# SCH_Hub-UDB_2025-02-06.net
KiCad netlist of a schematic drawn in EasyEDA
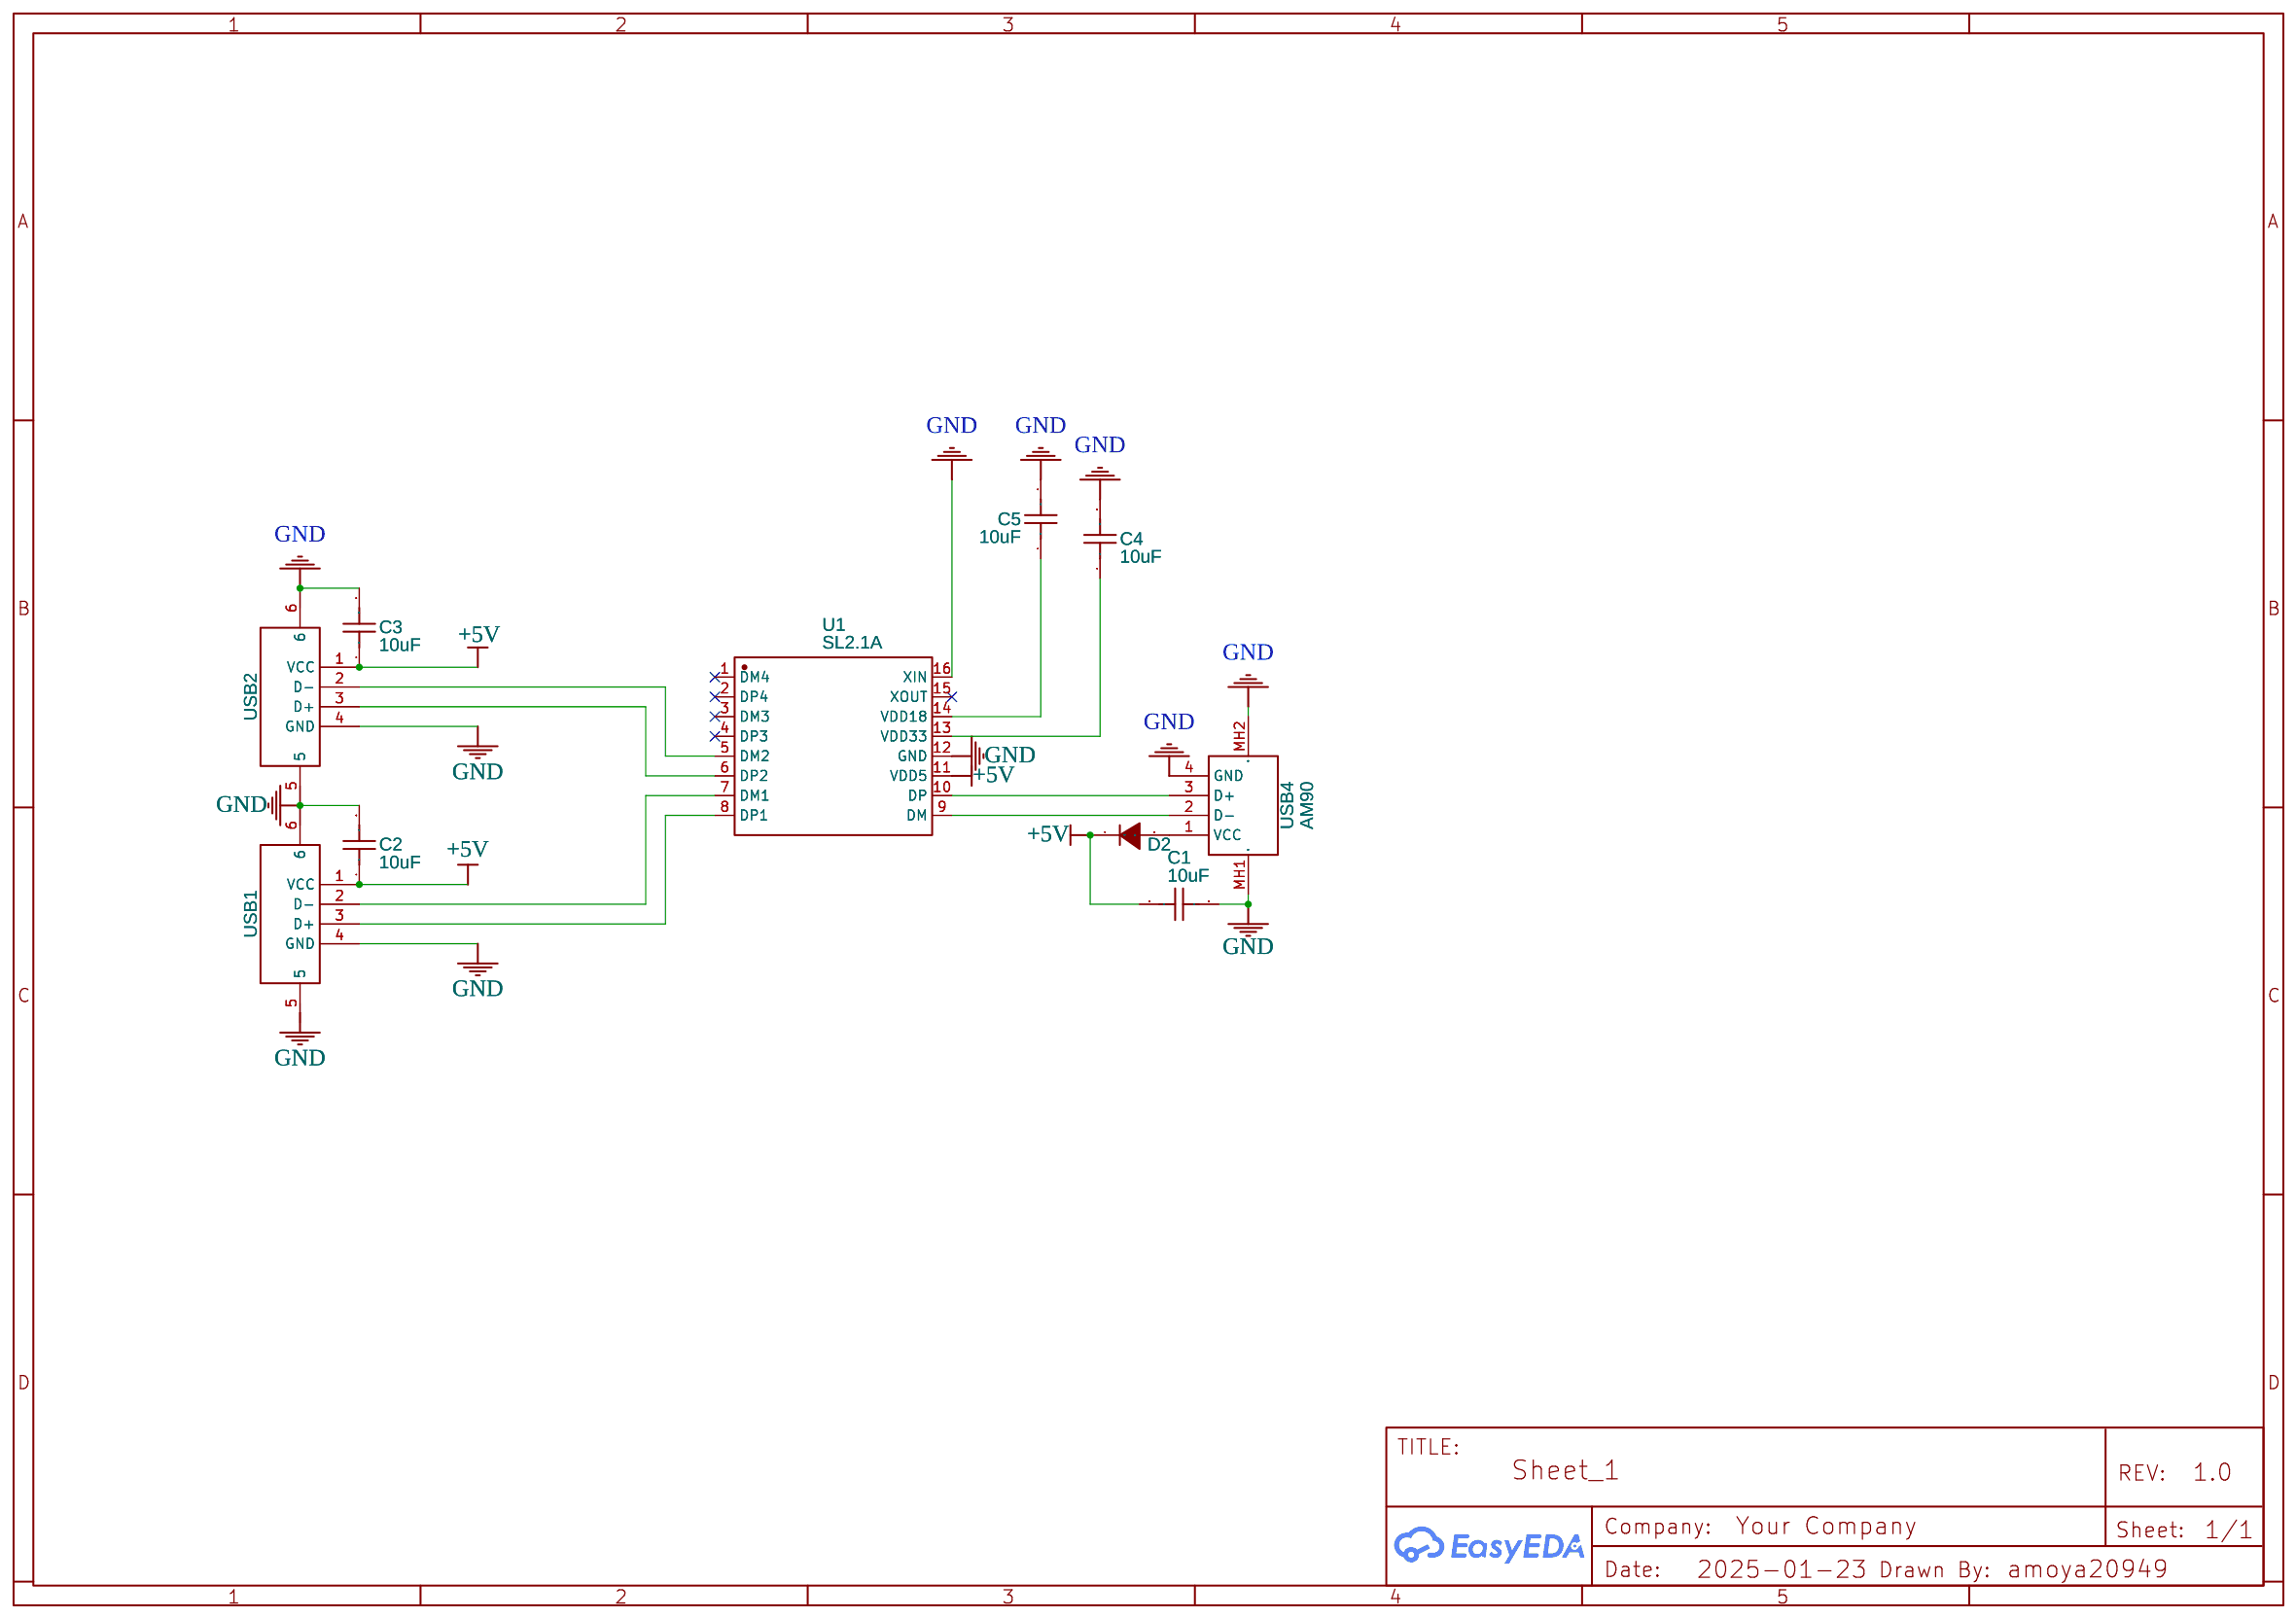
[diagram p0: schematic sheet]

(export (version "E")
  (design (tool "Eeschema 10.0.6"))
  (components
    (comp (ref "C1")
      (value "10uF")
      (fields
        (field (name "Manufacturer Part") "CL10A106KP8NNNC")
        (field (name "Manufacturer") "SAMSUNG(三星)")
      )
      (libsource (lib "") (part "CL10A106KP8NNNC_1"))
    )
    (comp (ref "C2")
      (value "10uF")
      (fields
        (field (name "Manufacturer Part") "CL10A106KP8NNNC")
        (field (name "Manufacturer") "SAMSUNG(三星)")
      )
      (libsource (lib "") (part "CL10A106KP8NNNC"))
    )
    (comp (ref "C3")
      (value "10uF")
      (fields
        (field (name "Manufacturer Part") "CL10A106KP8NNNC")
        (field (name "Manufacturer") "SAMSUNG(三星)")
      )
      (libsource (lib "") (part "CL10A106KP8NNNC"))
    )
    (comp (ref "C4")
      (value "10uF")
      (fields
        (field (name "Manufacturer Part") "CL10A106KP8NNNC")
        (field (name "Manufacturer") "SAMSUNG(三星)")
      )
      (libsource (lib "") (part "CL10A106KP8NNNC"))
    )
    (comp (ref "C5")
      (value "10uF")
      (fields
        (field (name "Manufacturer Part") "CL10A106KP8NNNC")
        (field (name "Manufacturer") "SAMSUNG(三星)")
      )
      (libsource (lib "") (part "CL10A106KP8NNNC_2"))
    )
    (comp (ref "D2")
      (value "NSR0320MW2T1G")
      (fields (field (name "Manufacturer") "onsemi(安森美)"))
      (libsource (lib "") (part "NSR0320MW2T1G"))
    )
    (comp (ref "U1")
      (value "SL2.1A")
      (fields (field (name "Manufacturer") "CoreChips(和芯润德)"))
      (libsource (lib "") (part "SL2.1A"))
    )
    (comp (ref "USB1")
      (value "USB-AF-90-14.4X13.6-H7.0-DIP")
      (fields (field (name "Manufacturer Part") "903-131A1011D10100") (field (name "Manufacturer") "精拓金"))
      (libsource (lib "") (part "USB-AF-90-14.4X13.6-H7.0-DIP"))
    )
    (comp (ref "USB2")
      (value "USB-AF-90-14.4X13.6-H7.0-DIP")
      (fields (field (name "Manufacturer Part") "903-131A1011D10100") (field (name "Manufacturer") "精拓金"))
      (libsource (lib "") (part "USB-AF-90-14.4X13.6-H7.0-DIP"))
    )
    (comp (ref "USB4")
      (value "AM90")
      (fields (field (name "Manufacturer") "SHOU HAN(首韩)"))
      (libsource (lib "") (part "AM90"))
    )
  )
  (nets
    (net (code "1") (name "+5V") (class "Default")
      (node (ref "C1") (pin "1") (pinfunction "1_1") (pintype "unspecified"))
      (node (ref "C2") (pin "1") (pinfunction "1_1") (pintype "unspecified"))
      (node (ref "C3") (pin "1") (pinfunction "1_1") (pintype "unspecified"))
      (node (ref "D2") (pin "1") (pinfunction "C_1") (pintype "unspecified"))
      (node (ref "U1") (pin "11") (pinfunction "VDD5_11") (pintype "unspecified"))
      (node (ref "USB1") (pin "1") (pinfunction "VCC_1") (pintype "unspecified"))
      (node (ref "USB2") (pin "1") (pinfunction "VCC_1") (pintype "unspecified"))
    )
    (net (code "2") (name "GND") (class "Default")
      (node (ref "C1") (pin "2") (pinfunction "2_2") (pintype "unspecified"))
      (node (ref "C2") (pin "2") (pinfunction "2_2") (pintype "unspecified"))
      (node (ref "C3") (pin "2") (pinfunction "2_2") (pintype "unspecified"))
      (node (ref "C4") (pin "2") (pinfunction "2_2") (pintype "unspecified"))
      (node (ref "C5") (pin "2") (pinfunction "2_2") (pintype "unspecified"))
      (node (ref "U1") (pin "12") (pinfunction "GND_12") (pintype "unspecified"))
      (node (ref "U1") (pin "16") (pinfunction "XIN_16") (pintype "unspecified"))
      (node (ref "USB1") (pin "4") (pinfunction "GND_4") (pintype "unspecified"))
      (node (ref "USB1") (pin "6") (pinfunction "6_6") (pintype "unspecified"))
      (node (ref "USB2") (pin "4") (pinfunction "GND_4") (pintype "unspecified"))
      (node (ref "USB2") (pin "5") (pinfunction "5_5") (pintype "unspecified"))
      (node (ref "USB2") (pin "6") (pinfunction "6_6") (pintype "unspecified"))
      (node (ref "USB4") (pin "4") (pinfunction "GND_4") (pintype "input"))
      (node (ref "USB4") (pin "MH1") (pinfunction "MH1_MH1") (pintype "unspecified"))
      (node (ref "USB4") (pin "MH2") (pinfunction "MH2_MH2") (pintype "unspecified"))
    )
    (net (code "3") (name "Net-(D2-A)") (class "Default")
      (node (ref "D2") (pin "2") (pinfunction "A_2") (pintype "unspecified"))
      (node (ref "USB4") (pin "1") (pinfunction "VCC_1") (pintype "input"))
    )
    (net (code "4") (name "Net-(U1-DM)") (class "Default")
      (node (ref "U1") (pin "9") (pinfunction "DM_9") (pintype "unspecified"))
      (node (ref "USB4") (pin "2") (pinfunction "D-_2") (pintype "input"))
    )
    (net (code "5") (name "Net-(U1-DM1)") (class "Default")
      (node (ref "U1") (pin "7") (pinfunction "DM1_7") (pintype "unspecified"))
      (node (ref "USB1") (pin "2") (pinfunction "D-_2") (pintype "unspecified"))
    )
    (net (code "6") (name "Net-(U1-DM2)") (class "Default")
      (node (ref "U1") (pin "5") (pinfunction "DM2_5") (pintype "unspecified"))
      (node (ref "USB2") (pin "2") (pinfunction "D-_2") (pintype "unspecified"))
    )
    (net (code "7") (name "Net-(U1-DP)") (class "Default")
      (node (ref "U1") (pin "10") (pinfunction "DP_10") (pintype "unspecified"))
      (node (ref "USB4") (pin "3") (pinfunction "D+_3") (pintype "input"))
    )
    (net (code "8") (name "Net-(U1-DP1)") (class "Default")
      (node (ref "U1") (pin "8") (pinfunction "DP1_8") (pintype "unspecified"))
      (node (ref "USB1") (pin "3") (pinfunction "D+_3") (pintype "unspecified"))
    )
    (net (code "9") (name "Net-(U1-DP2)") (class "Default")
      (node (ref "U1") (pin "6") (pinfunction "DP2_6") (pintype "unspecified"))
      (node (ref "USB2") (pin "3") (pinfunction "D+_3") (pintype "unspecified"))
    )
    (net (code "10") (name "Net-(U1-VDD18)") (class "Default")
      (node (ref "C5") (pin "1") (pinfunction "1_1") (pintype "unspecified"))
      (node (ref "U1") (pin "14") (pinfunction "VDD18_14") (pintype "unspecified"))
    )
    (net (code "11") (name "Net-(U1-VDD33)") (class "Default")
      (node (ref "C4") (pin "1") (pinfunction "1_1") (pintype "unspecified"))
      (node (ref "U1") (pin "13") (pinfunction "VDD33_13") (pintype "unspecified"))
    )
    (net (code "12") (name "unconnected-(U1-DM3-Pad3)") (class "Default")
      (node (ref "U1") (pin "3") (pinfunction "DM3_3") (pintype "unspecified+no_connect"))
    )
    (net (code "13") (name "unconnected-(U1-DM4-Pad1)") (class "Default")
      (node (ref "U1") (pin "1") (pinfunction "DM4_1") (pintype "unspecified+no_connect"))
    )
    (net (code "14") (name "unconnected-(U1-DP3-Pad4)") (class "Default")
      (node (ref "U1") (pin "4") (pinfunction "DP3_4") (pintype "unspecified+no_connect"))
    )
    (net (code "15") (name "unconnected-(U1-DP4-Pad2)") (class "Default")
      (node (ref "U1") (pin "2") (pinfunction "DP4_2") (pintype "unspecified+no_connect"))
    )
    (net (code "16") (name "unconnected-(U1-XOUT-Pad15)") (class "Default")
      (node (ref "U1") (pin "15") (pinfunction "XOUT_15") (pintype "unspecified+no_connect"))
    )
    (net (code "17") (name "unconnected-(USB1-Pad5)") (class "Default")
      (node (ref "USB1") (pin "5") (pinfunction "5_5") (pintype "unspecified"))
    )
  )
)
